# BT_atmega_v_1_2.net
KiCad netlist of a schematic drawn in EAGLE
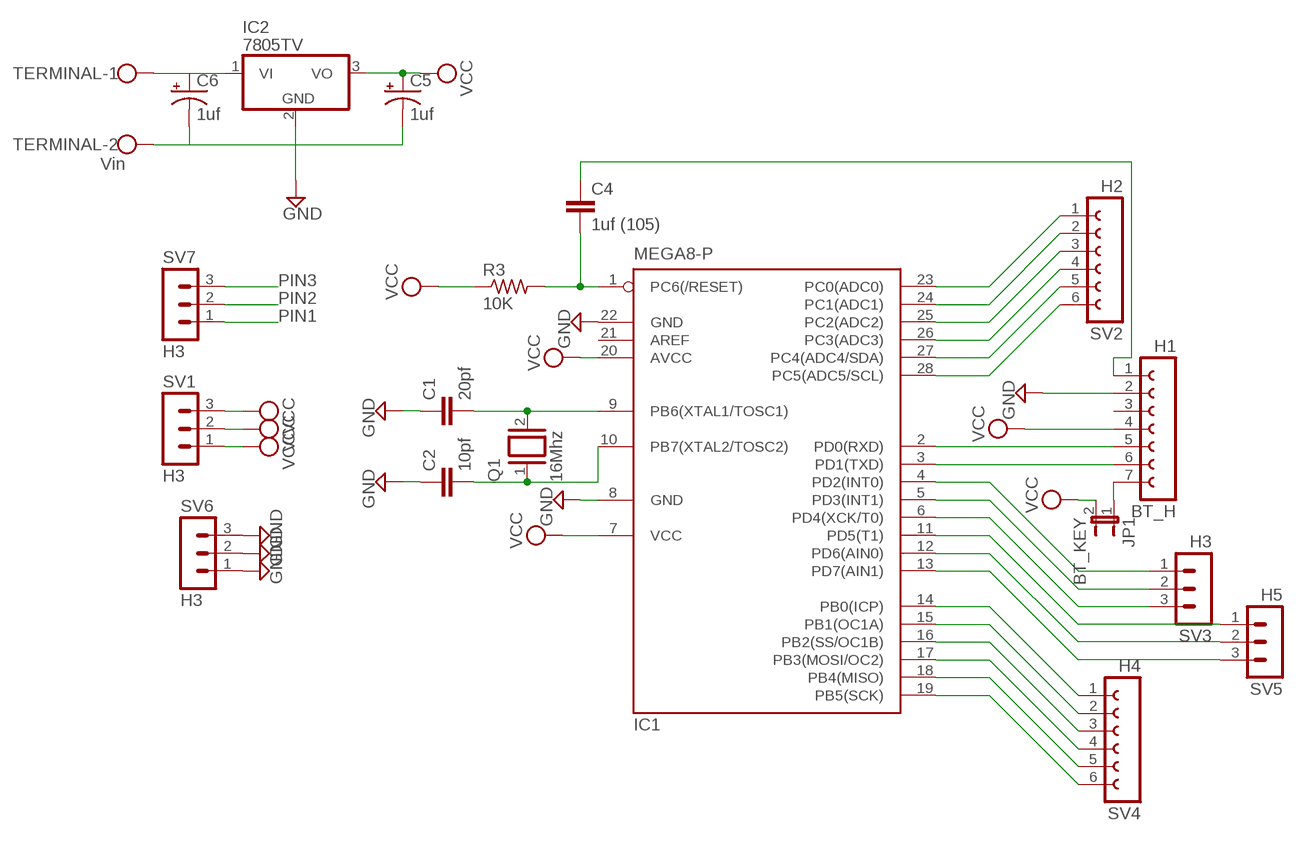
[diagram p0: schematic, sheet 1]

(export (version "E")
  (design (tool "Eeschema 10.0.6"))
  (components
    (comp (ref "BT_H")
      (value "H1")
      (footprint "eagle-import:FE07")
      (libsource (lib "eagle-import") (part "FE07-1"))
    )
    (comp (ref "C1")
      (value "20pf")
      (footprint "eagle-import:C2.5-2")
      (libsource (lib "eagle-import") (part "C2.5/2"))
    )
    (comp (ref "C2")
      (value "10pf")
      (footprint "eagle-import:C2.5-2")
      (libsource (lib "eagle-import") (part "C2.5/2"))
    )
    (comp (ref "C4")
      (value "1uf (105)")
      (footprint "eagle-import:C2.5-2")
      (libsource (lib "eagle-import") (part "C2.5/2"))
    )
    (comp (ref "C5")
      (value "1uf")
      (footprint "eagle-import:E5-4")
      (libsource (lib "eagle-import") (part "CPOL-USE5-4"))
    )
    (comp (ref "C6")
      (value "1uf")
      (footprint "eagle-import:E5-4")
      (libsource (lib "eagle-import") (part "CPOL-USE5-4"))
    )
    (comp (ref "IC1")
      (value "MEGA8-P")
      (footprint "eagle-import:DIL28-3")
      (libsource (lib "eagle-import") (part "MEGA8-P"))
    )
    (comp (ref "IC2")
      (value "7805TV")
      (footprint "eagle-import:TO220V")
      (libsource (lib "eagle-import") (part "78TV05"))
    )
    (comp (ref "JP1")
      (value "BT_KEY")
      (footprint "eagle-import:JP1")
      (libsource (lib "eagle-import") (part "JP1E"))
    )
    (comp (ref "Q1")
      (value "16Mhz")
      (footprint "eagle-import:QS")
      (libsource (lib "eagle-import") (part "XTAL/S"))
    )
    (comp (ref "R3")
      (value "10K")
      (footprint "eagle-import:0204_5")
      (libsource (lib "eagle-import") (part "R-US_0204/5"))
    )
    (comp (ref "SV1")
      (value "H3")
      (footprint "eagle-import:MA03-1")
      (libsource (lib "eagle-import") (part "MA03-1"))
    )
    (comp (ref "SV2")
      (value "H2")
      (footprint "eagle-import:FE06")
      (libsource (lib "eagle-import") (part "FE06-1"))
    )
    (comp (ref "SV3")
      (value "H3")
      (footprint "eagle-import:MA03-1")
      (libsource (lib "eagle-import") (part "MA03-1"))
    )
    (comp (ref "SV4")
      (value "H4")
      (footprint "eagle-import:FE06")
      (libsource (lib "eagle-import") (part "FE06-1"))
    )
    (comp (ref "SV5")
      (value "H5")
      (footprint "eagle-import:MA03-1")
      (libsource (lib "eagle-import") (part "MA03-1"))
    )
    (comp (ref "SV6")
      (value "H3")
      (footprint "eagle-import:MA03-1")
      (libsource (lib "eagle-import") (part "MA03-1"))
    )
    (comp (ref "SV7")
      (value "H3")
      (footprint "eagle-import:MA03-1")
      (libsource (lib "eagle-import") (part "MA03-1"))
    )
    (comp (ref "TERMINAL")
      (value "Vin")
      (footprint "eagle-import:W237-102")
      (fields (field (name "MPN") "237-102"))
      (libsource (lib "eagle-import") (part "W237-102"))
    )
  )
  (nets
    (net (code "1") (name "/PIN1") (class "Default")
      (node (ref "C4") (pin "2") (pinfunction "2_2") (pintype "passive"))
      (node (ref "IC1") (pin "1") (pinfunction "PC6(/RESET)_1") (pintype "bidirectional"))
      (node (ref "R3") (pin "2") (pinfunction "2_2") (pintype "passive"))
      (node (ref "SV7") (pin "1") (pinfunction "1_1") (pintype "passive"))
    )
    (net (code "2") (name "/PIN2") (class "Default")
      (node (ref "BT_H") (pin "5") (pinfunction "5_5") (pintype "passive"))
      (node (ref "IC1") (pin "2") (pinfunction "PD0(RXD)_2") (pintype "bidirectional"))
      (node (ref "SV7") (pin "2") (pinfunction "2_2") (pintype "passive"))
    )
    (net (code "3") (name "/PIN3") (class "Default")
      (node (ref "BT_H") (pin "6") (pinfunction "6_6") (pintype "passive"))
      (node (ref "IC1") (pin "3") (pinfunction "PD1(TXD)_3") (pintype "bidirectional"))
      (node (ref "SV7") (pin "3") (pinfunction "3_3") (pintype "passive"))
    )
    (net (code "4") (name "GND") (class "Default")
      (node (ref "BT_H") (pin "2") (pinfunction "2_2") (pintype "passive"))
      (node (ref "C1") (pin "1") (pinfunction "1_1") (pintype "passive"))
      (node (ref "C2") (pin "1") (pinfunction "1_1") (pintype "passive"))
      (node (ref "C5") (pin "-") (pinfunction "-_-") (pintype "passive"))
      (node (ref "C6") (pin "-") (pinfunction "-_-") (pintype "passive"))
      (node (ref "IC1") (pin "22") (pinfunction "GND_22") (pintype "power_in"))
      (node (ref "IC1") (pin "8") (pinfunction "GND_8") (pintype "power_in"))
      (node (ref "IC2") (pin "2") (pinfunction "GND_2") (pintype "passive"))
      (node (ref "SV6") (pin "1") (pinfunction "1_1") (pintype "passive"))
      (node (ref "SV6") (pin "2") (pinfunction "2_2") (pintype "passive"))
      (node (ref "SV6") (pin "3") (pinfunction "3_3") (pintype "passive"))
      (node (ref "TERMINAL") (pin "2") (pinfunction "KL_2") (pintype "passive"))
    )
    (net (code "5") (name "Net-(BT_H-Pad1)") (class "Default")
      (node (ref "BT_H") (pin "1") (pinfunction "1_1") (pintype "passive"))
      (node (ref "C4") (pin "1") (pinfunction "1_1") (pintype "passive"))
    )
    (net (code "6") (name "Net-(BT_H-Pad7)") (class "Default")
      (node (ref "BT_H") (pin "7") (pinfunction "7_7") (pintype "passive"))
      (node (ref "JP1") (pin "1") (pinfunction "1_1") (pintype "passive"))
    )
    (net (code "7") (name "Net-(IC1-PB0(ICP))") (class "Default")
      (node (ref "IC1") (pin "14") (pinfunction "PB0(ICP)_14") (pintype "bidirectional"))
      (node (ref "SV4") (pin "1") (pinfunction "1_1") (pintype "passive"))
    )
    (net (code "8") (name "Net-(IC1-PB1(OC1A))") (class "Default")
      (node (ref "IC1") (pin "15") (pinfunction "PB1(OC1A)_15") (pintype "bidirectional"))
      (node (ref "SV4") (pin "2") (pinfunction "2_2") (pintype "passive"))
    )
    (net (code "9") (name "Net-(IC1-PB2(SS{slash}OC1B))") (class "Default")
      (node (ref "IC1") (pin "16") (pinfunction "PB2(SS/OC1B)_16") (pintype "bidirectional"))
      (node (ref "SV4") (pin "3") (pinfunction "3_3") (pintype "passive"))
    )
    (net (code "10") (name "Net-(IC1-PB3(MOSI{slash}OC2))") (class "Default")
      (node (ref "IC1") (pin "17") (pinfunction "PB3(MOSI/OC2)_17") (pintype "bidirectional"))
      (node (ref "SV4") (pin "4") (pinfunction "4_4") (pintype "passive"))
    )
    (net (code "11") (name "Net-(IC1-PB4(MISO))") (class "Default")
      (node (ref "IC1") (pin "18") (pinfunction "PB4(MISO)_18") (pintype "bidirectional"))
      (node (ref "SV4") (pin "5") (pinfunction "5_5") (pintype "passive"))
    )
    (net (code "12") (name "Net-(IC1-PB5(SCK))") (class "Default")
      (node (ref "IC1") (pin "19") (pinfunction "PB5(SCK)_19") (pintype "bidirectional"))
      (node (ref "SV4") (pin "6") (pinfunction "6_6") (pintype "passive"))
    )
    (net (code "13") (name "Net-(IC1-PB6(XTAL1{slash}TOSC1))") (class "Default")
      (node (ref "C1") (pin "2") (pinfunction "2_2") (pintype "passive"))
      (node (ref "IC1") (pin "9") (pinfunction "PB6(XTAL1/TOSC1)_9") (pintype "bidirectional"))
      (node (ref "Q1") (pin "2") (pinfunction "2_2") (pintype "passive"))
    )
    (net (code "14") (name "Net-(IC1-PB7(XTAL2{slash}TOSC2))") (class "Default")
      (node (ref "C2") (pin "2") (pinfunction "2_2") (pintype "passive"))
      (node (ref "IC1") (pin "10") (pinfunction "PB7(XTAL2/TOSC2)_10") (pintype "bidirectional"))
      (node (ref "Q1") (pin "1") (pinfunction "1_1") (pintype "passive"))
    )
    (net (code "15") (name "Net-(IC1-PC0(ADC0))") (class "Default")
      (node (ref "IC1") (pin "23") (pinfunction "PC0(ADC0)_23") (pintype "bidirectional"))
      (node (ref "SV2") (pin "1") (pinfunction "1_1") (pintype "passive"))
    )
    (net (code "16") (name "Net-(IC1-PC1(ADC1))") (class "Default")
      (node (ref "IC1") (pin "24") (pinfunction "PC1(ADC1)_24") (pintype "bidirectional"))
      (node (ref "SV2") (pin "2") (pinfunction "2_2") (pintype "passive"))
    )
    (net (code "17") (name "Net-(IC1-PC2(ADC2))") (class "Default")
      (node (ref "IC1") (pin "25") (pinfunction "PC2(ADC2)_25") (pintype "bidirectional"))
      (node (ref "SV2") (pin "3") (pinfunction "3_3") (pintype "passive"))
    )
    (net (code "18") (name "Net-(IC1-PC3(ADC3))") (class "Default")
      (node (ref "IC1") (pin "26") (pinfunction "PC3(ADC3)_26") (pintype "bidirectional"))
      (node (ref "SV2") (pin "4") (pinfunction "4_4") (pintype "passive"))
    )
    (net (code "19") (name "Net-(IC1-PC4(ADC4{slash}SDA))") (class "Default")
      (node (ref "IC1") (pin "27") (pinfunction "PC4(ADC4/SDA)_27") (pintype "bidirectional"))
      (node (ref "SV2") (pin "5") (pinfunction "5_5") (pintype "passive"))
    )
    (net (code "20") (name "Net-(IC1-PC5(ADC5{slash}SCL))") (class "Default")
      (node (ref "IC1") (pin "28") (pinfunction "PC5(ADC5/SCL)_28") (pintype "bidirectional"))
      (node (ref "SV2") (pin "6") (pinfunction "6_6") (pintype "passive"))
    )
    (net (code "21") (name "Net-(IC1-PD2(INT0))") (class "Default")
      (node (ref "IC1") (pin "4") (pinfunction "PD2(INT0)_4") (pintype "bidirectional"))
      (node (ref "SV3") (pin "1") (pinfunction "1_1") (pintype "passive"))
    )
    (net (code "22") (name "Net-(IC1-PD3(INT1))") (class "Default")
      (node (ref "IC1") (pin "5") (pinfunction "PD3(INT1)_5") (pintype "bidirectional"))
      (node (ref "SV3") (pin "2") (pinfunction "2_2") (pintype "passive"))
    )
    (net (code "23") (name "Net-(IC1-PD4(XCK{slash}T0))") (class "Default")
      (node (ref "IC1") (pin "6") (pinfunction "PD4(XCK/T0)_6") (pintype "bidirectional"))
      (node (ref "SV3") (pin "3") (pinfunction "3_3") (pintype "passive"))
    )
    (net (code "24") (name "Net-(IC1-PD5(T1))") (class "Default")
      (node (ref "IC1") (pin "11") (pinfunction "PD5(T1)_11") (pintype "bidirectional"))
      (node (ref "SV5") (pin "1") (pinfunction "1_1") (pintype "passive"))
    )
    (net (code "25") (name "Net-(IC1-PD6(AIN0))") (class "Default")
      (node (ref "IC1") (pin "12") (pinfunction "PD6(AIN0)_12") (pintype "bidirectional"))
      (node (ref "SV5") (pin "2") (pinfunction "2_2") (pintype "passive"))
    )
    (net (code "26") (name "Net-(IC1-PD7(AIN1))") (class "Default")
      (node (ref "IC1") (pin "13") (pinfunction "PD7(AIN1)_13") (pintype "bidirectional"))
      (node (ref "SV5") (pin "3") (pinfunction "3_3") (pintype "passive"))
    )
    (net (code "27") (name "Net-(IC2-VI)") (class "Default")
      (node (ref "C6") (pin "+") (pinfunction "+_+") (pintype "passive"))
      (node (ref "IC2") (pin "1") (pinfunction "VI_1") (pintype "input"))
      (node (ref "TERMINAL") (pin "1") (pinfunction "KL_1") (pintype "passive"))
    )
    (net (code "28") (name "VCC") (class "Default")
      (node (ref "BT_H") (pin "4") (pinfunction "4_4") (pintype "passive"))
      (node (ref "C5") (pin "+") (pinfunction "+_+") (pintype "passive"))
      (node (ref "IC1") (pin "20") (pinfunction "AVCC_20") (pintype "power_in"))
      (node (ref "IC1") (pin "7") (pinfunction "VCC_7") (pintype "power_in"))
      (node (ref "IC2") (pin "3") (pinfunction "VO_3") (pintype "passive"))
      (node (ref "JP1") (pin "2") (pinfunction "2_2") (pintype "passive"))
      (node (ref "R3") (pin "1") (pinfunction "1_1") (pintype "passive"))
      (node (ref "SV1") (pin "1") (pinfunction "1_1") (pintype "passive"))
      (node (ref "SV1") (pin "2") (pinfunction "2_2") (pintype "passive"))
      (node (ref "SV1") (pin "3") (pinfunction "3_3") (pintype "passive"))
    )
    (net (code "29") (name "unconnected-(BT_H-Pad3)") (class "Default")
      (node (ref "BT_H") (pin "3") (pinfunction "3_3") (pintype "passive"))
    )
    (net (code "30") (name "unconnected-(IC1-AREF-Pad21)") (class "Default")
      (node (ref "IC1") (pin "21") (pinfunction "AREF_21") (pintype "passive"))
    )
  )
)
